# goprocontrol.net
KiCad netlist of a schematic drawn in EAGLE
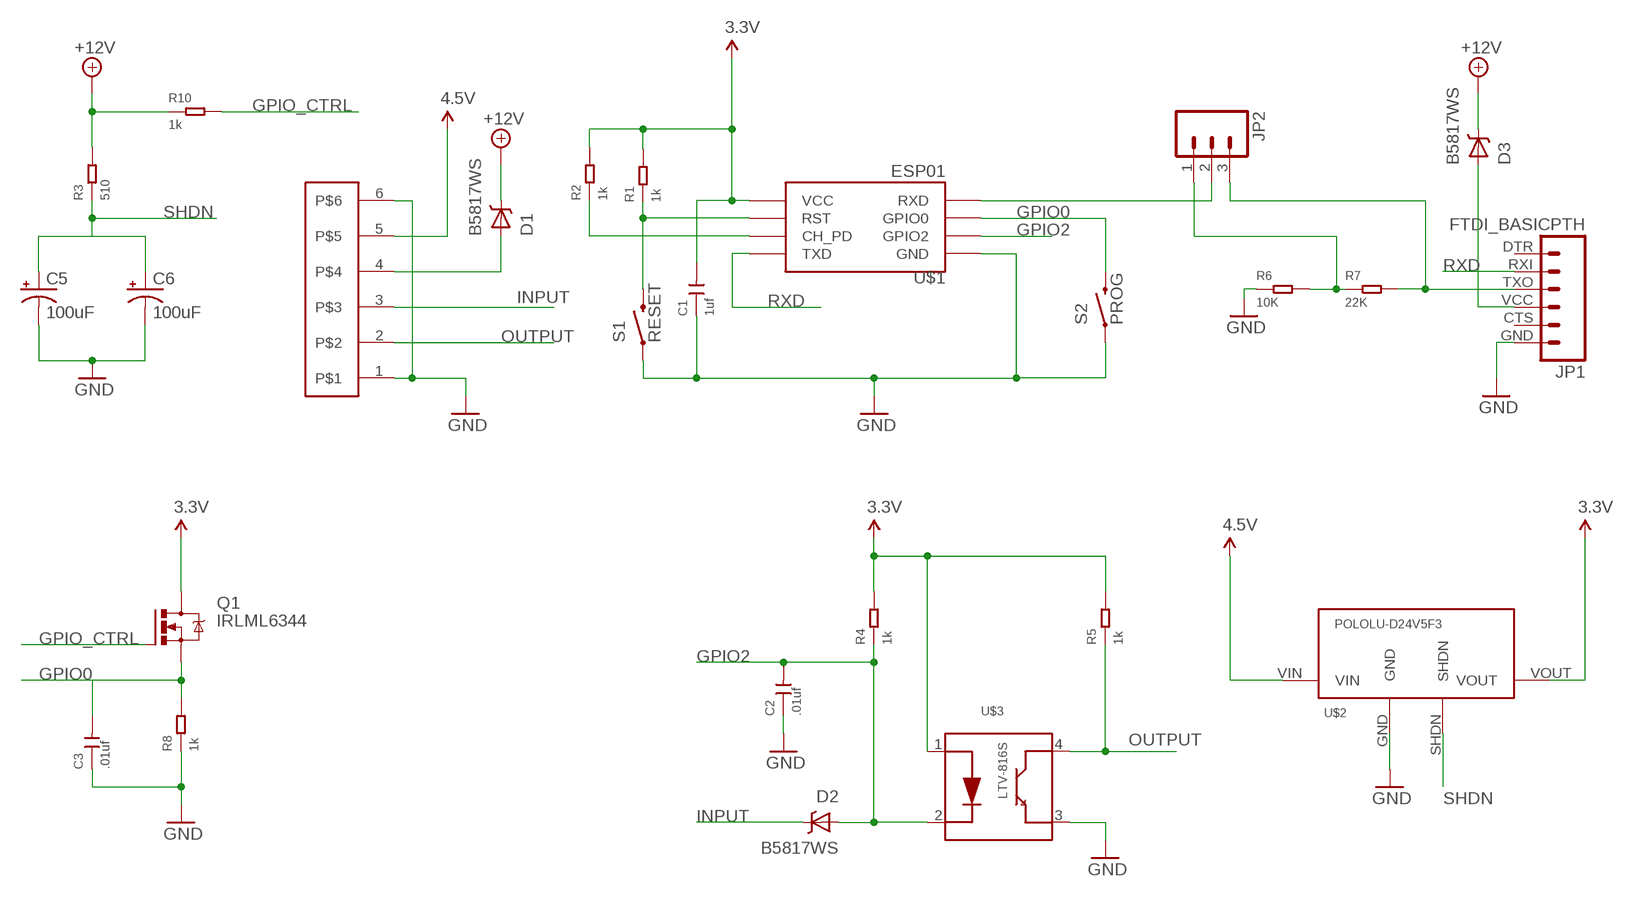
[diagram p0: schematic, sheet 1]

(export (version "E")
  (design (tool "Eeschema 10.0.6"))
  (components
    (comp (ref "C1")
      (value "1uf")
      (footprint "eagle-import:C0805")
      (fields (field (name "MPN") "CC0805KKX7R8BB105"))
      (libsource (lib "eagle-import") (part "CERAMIC-1UF-25V-10%-X7R(0805)"))
    )
    (comp (ref "C2")
      (value ".01uf")
      (footprint "eagle-import:C0805")
      (fields (field (name "MPN") "CC0805KKX7R8BB105"))
      (libsource (lib "eagle-import") (part "CERAMIC-1UF-25V-10%-X7R(0805)"))
    )
    (comp (ref "C3")
      (value ".01uf")
      (footprint "eagle-import:C0805")
      (fields (field (name "MPN") "CC0805KKX7R8BB105"))
      (libsource (lib "eagle-import") (part "CERAMIC-1UF-25V-10%-X7R(0805)"))
    )
    (comp (ref "C5")
      (value "100uF")
      (footprint "eagle-import:CPOL-RADIAL-100UF-25V")
      (libsource (lib "eagle-import") (part "CAP_POLPTH1"))
    )
    (comp (ref "C6")
      (value "100uF")
      (footprint "eagle-import:CPOL-RADIAL-100UF-25V")
      (libsource (lib "eagle-import") (part "CAP_POLPTH1"))
    )
    (comp (ref "D1")
      (value "B5817WS")
      (footprint "eagle-import:SOD-323")
      (libsource (lib "eagle-import") (part "SCHOTTKY-DIODE"))
    )
    (comp (ref "D2")
      (value "B5817WS")
      (footprint "eagle-import:SOD-323")
      (libsource (lib "eagle-import") (part "SCHOTTKY-DIODE"))
    )
    (comp (ref "D3")
      (value "B5817WS")
      (footprint "eagle-import:SOD-323")
      (libsource (lib "eagle-import") (part "SCHOTTKY-DIODE"))
    )
    (comp (ref "JP1")
      (value "FTDI_BASICPTH")
      (footprint "eagle-import:FTDI_BASIC")
      (libsource (lib "eagle-import") (part "FTDI_BASICPTH"))
    )
    (comp (ref "JP2")
      (value "M03PTH")
      (footprint "eagle-import:1X03")
      (libsource (lib "eagle-import") (part "M03PTH"))
    )
    (comp (ref "Q1")
      (value "IRLML6344")
      (footprint "eagle-import:SOT23")
      (libsource (lib "eagle-import") (part "IRLML6344"))
    )
    (comp (ref "R1")
      (value "1k")
      (footprint "eagle-import:R0805")
      (fields (field (name "MPN") "RC0805FR-0710KL"))
      (libsource (lib "eagle-import") (part "SMD-RES-10K-1%-1/8W(0805)"))
    )
    (comp (ref "R2")
      (value "1k")
      (footprint "eagle-import:R0805")
      (fields (field (name "MPN") "RC0805FR-0710KL"))
      (libsource (lib "eagle-import") (part "SMD-RES-10K-1%-1/8W(0805)"))
    )
    (comp (ref "R3")
      (value "510")
      (footprint "eagle-import:R0805")
      (fields (field (name "MPN") "RC0805FR-0710KL"))
      (libsource (lib "eagle-import") (part "SMD-RES-10K-1%-1/8W(0805)"))
    )
    (comp (ref "R4")
      (value "1k")
      (footprint "eagle-import:R0805")
      (fields (field (name "MPN") "RC0805FR-0710KL"))
      (libsource (lib "eagle-import") (part "SMD-RES-10K-1%-1/8W(0805)"))
    )
    (comp (ref "R5")
      (value "1k")
      (footprint "eagle-import:R0805")
      (fields (field (name "MPN") "RC0805FR-0710KL"))
      (libsource (lib "eagle-import") (part "SMD-RES-10K-1%-1/8W(0805)"))
    )
    (comp (ref "R6")
      (value "10K")
      (footprint "eagle-import:R0805")
      (fields (field (name "MPN") "RC0805FR-0710KL"))
      (libsource (lib "eagle-import") (part "SMD-RES-10K-1%-1/8W(0805)"))
    )
    (comp (ref "R7")
      (value "22K")
      (footprint "eagle-import:R0805")
      (fields (field (name "MPN") "RC0805JR-0722KL"))
      (libsource (lib "eagle-import") (part "SMD-RES-22K-5%-1/8W(0805)"))
    )
    (comp (ref "R8")
      (value "1k")
      (footprint "eagle-import:R0805")
      (fields (field (name "MPN") "RC0805FR-07100KL"))
      (libsource (lib "eagle-import") (part "SMD-RES-100K-1%-1/8W(0805)"))
    )
    (comp (ref "R10")
      (value "1k")
      (footprint "eagle-import:R0805")
      (fields (field (name "MPN") "RC0805FR-0710KL"))
      (libsource (lib "eagle-import") (part "SMD-RES-10K-1%-1/8W(0805)"))
    )
    (comp (ref "S1")
      (value "RESET")
      (footprint "eagle-import:TACTILE-PTH")
      (libsource (lib "eagle-import") (part "SWITCH-MOMENTARY-2PTH"))
    )
    (comp (ref "S2")
      (value "PROG")
      (footprint "eagle-import:TACTILE-PTH")
      (libsource (lib "eagle-import") (part "SWITCH-MOMENTARY-2PTH"))
    )
    (comp (ref "U$1")
      (value "ESP01")
      (footprint "eagle-import:ESP01")
      (libsource (lib "eagle-import") (part "ESP01"))
    )
    (comp (ref "U$2")
      (value "POLOLU-D24V5F3")
      (footprint "eagle-import:POLOLU-D24V5FX")
      (libsource (lib "eagle-import") (part "POLOLU-D24V5FD24V5F"))
    )
    (comp (ref "U$3")
      (value "LTV-816S")
      (footprint "eagle-import:SMD4-2.54-4.6X6.5MM")
      (libsource (lib "eagle-import") (part "SMD-PHOTOCOUPLER-5KV-LTV-816S(4P-4.6X6.5MM)"))
    )
    (comp (ref "U$4")
      (value "TERM-BLOCK-P6-3.5")
      (footprint "eagle-import:TERM-6P-3.5")
      (libsource (lib "eagle-import") (part "TERM-BLOCK-P6-3.5"))
    )
  )
  (nets
    (net (code "1") (name "+12V") (class "Default")
      (node (ref "D1") (pin "C1") (pinfunction "C_C1") (pintype "output"))
      (node (ref "D3") (pin "C1") (pinfunction "C_C1") (pintype "output"))
      (node (ref "R10") (pin "1") (pinfunction "1_1") (pintype "passive"))
      (node (ref "R3") (pin "2") (pinfunction "2_2") (pintype "passive"))
    )
    (net (code "2") (name "/GPIO0") (class "Default")
      (node (ref "C3") (pin "2") (pinfunction "2_2") (pintype "passive"))
      (node (ref "Q1") (pin "2") (pinfunction "S_2") (pintype "passive"))
      (node (ref "R8") (pin "2") (pinfunction "2_2") (pintype "passive"))
      (node (ref "S2") (pin "3") (pinfunction "2_3") (pintype "passive"))
      (node (ref "U$1") (pin "GPIO0") (pinfunction "GPIO0_GPIO0") (pintype "bidirectional"))
    )
    (net (code "3") (name "/GPIO2") (class "Default")
      (node (ref "C2") (pin "2") (pinfunction "2_2") (pintype "passive"))
      (node (ref "D2") (pin "A1") (pinfunction "A_A1") (pintype "input"))
      (node (ref "R4") (pin "1") (pinfunction "1_1") (pintype "passive"))
      (node (ref "U$1") (pin "GPIO2") (pinfunction "GPIO2_GPIO2") (pintype "bidirectional"))
      (node (ref "U$3") (pin "2") (pinfunction "CATHODE_2") (pintype "bidirectional"))
    )
    (net (code "4") (name "/GPIO_CTRL") (class "Default")
      (node (ref "Q1") (pin "1") (pinfunction "G_1") (pintype "passive"))
      (node (ref "R10") (pin "2") (pinfunction "2_2") (pintype "passive"))
    )
    (net (code "5") (name "/INPUT") (class "Default")
      (node (ref "D2") (pin "C1") (pinfunction "C_C1") (pintype "output"))
      (node (ref "U$4") (pin "3") (pinfunction "P$3_3") (pintype "bidirectional"))
    )
    (net (code "6") (name "/OUTPUT") (class "Default")
      (node (ref "R5") (pin "1") (pinfunction "1_1") (pintype "passive"))
      (node (ref "U$3") (pin "4") (pinfunction "COLLECTOR_4") (pintype "bidirectional"))
      (node (ref "U$4") (pin "2") (pinfunction "P$2_2") (pintype "bidirectional"))
    )
    (net (code "7") (name "/RXD") (class "Default")
      (node (ref "JP1") (pin "RXI") (pinfunction "2_RXI") (pintype "passive"))
      (node (ref "U$1") (pin "TX") (pinfunction "TXD_TX") (pintype "bidirectional"))
    )
    (net (code "8") (name "/SHDN") (class "Default")
      (node (ref "C5") (pin "1") (pinfunction "+_1") (pintype "passive"))
      (node (ref "C6") (pin "1") (pinfunction "+_1") (pintype "passive"))
      (node (ref "R3") (pin "1") (pinfunction "1_1") (pintype "passive"))
      (node (ref "U$2") (pin "SHDN") (pinfunction "SHDN_SHDN") (pintype "input"))
    )
    (net (code "9") (name "3.3V") (class "Default")
      (node (ref "C1") (pin "2") (pinfunction "2_2") (pintype "passive"))
      (node (ref "Q1") (pin "3") (pinfunction "D_3") (pintype "passive"))
      (node (ref "R1") (pin "2") (pinfunction "2_2") (pintype "passive"))
      (node (ref "R2") (pin "2") (pinfunction "2_2") (pintype "passive"))
      (node (ref "R4") (pin "2") (pinfunction "2_2") (pintype "passive"))
      (node (ref "R5") (pin "2") (pinfunction "2_2") (pintype "passive"))
      (node (ref "U$1") (pin "VCC") (pinfunction "VCC_VCC") (pintype "bidirectional"))
      (node (ref "U$2") (pin "VOUT") (pinfunction "VOUT_VOUT") (pintype "power_in"))
      (node (ref "U$3") (pin "1") (pinfunction "ANODE_1") (pintype "bidirectional"))
    )
    (net (code "10") (name "4.5V") (class "Default")
      (node (ref "U$2") (pin "VIN") (pinfunction "VIN_VIN") (pintype "input"))
      (node (ref "U$4") (pin "5") (pinfunction "P$5_5") (pintype "bidirectional"))
    )
    (net (code "11") (name "GND") (class "Default")
      (node (ref "C1") (pin "1") (pinfunction "1_1") (pintype "passive"))
      (node (ref "C2") (pin "1") (pinfunction "1_1") (pintype "passive"))
      (node (ref "C3") (pin "1") (pinfunction "1_1") (pintype "passive"))
      (node (ref "C5") (pin "2") (pinfunction "-_2") (pintype "passive"))
      (node (ref "C6") (pin "2") (pinfunction "-_2") (pintype "passive"))
      (node (ref "JP1") (pin "GND") (pinfunction "6_GND") (pintype "passive"))
      (node (ref "R6") (pin "1") (pinfunction "1_1") (pintype "passive"))
      (node (ref "R8") (pin "1") (pinfunction "1_1") (pintype "passive"))
      (node (ref "S1") (pin "1") (pinfunction "1_1") (pintype "passive"))
      (node (ref "S2") (pin "1") (pinfunction "1_1") (pintype "passive"))
      (node (ref "U$1") (pin "GND") (pinfunction "GND_GND") (pintype "bidirectional"))
      (node (ref "U$2") (pin "GND") (pinfunction "GND_GND") (pintype "power_in"))
      (node (ref "U$3") (pin "3") (pinfunction "EMITER_3") (pintype "bidirectional"))
      (node (ref "U$4") (pin "1") (pinfunction "P$1_1") (pintype "bidirectional"))
      (node (ref "U$4") (pin "6") (pinfunction "P$6_6") (pintype "bidirectional"))
    )
    (net (code "12") (name "Net-(D1-A)") (class "Default")
      (node (ref "D1") (pin "A1") (pinfunction "A_A1") (pintype "input"))
      (node (ref "U$4") (pin "4") (pinfunction "P$4_4") (pintype "bidirectional"))
    )
    (net (code "13") (name "Net-(D3-A)") (class "Default")
      (node (ref "D3") (pin "A1") (pinfunction "A_A1") (pintype "input"))
      (node (ref "JP1") (pin "VCC") (pinfunction "4_VCC") (pintype "passive"))
    )
    (net (code "14") (name "Net-(JP1-3)") (class "Default")
      (node (ref "JP1") (pin "TXO") (pinfunction "3_TXO") (pintype "passive"))
      (node (ref "JP2") (pin "3") (pinfunction "3_3") (pintype "passive"))
      (node (ref "R7") (pin "2") (pinfunction "2_2") (pintype "passive"))
    )
    (net (code "15") (name "Net-(JP2-Pad1)") (class "Default")
      (node (ref "JP2") (pin "1") (pinfunction "1_1") (pintype "passive"))
      (node (ref "R6") (pin "2") (pinfunction "2_2") (pintype "passive"))
      (node (ref "R7") (pin "1") (pinfunction "1_1") (pintype "passive"))
    )
    (net (code "16") (name "Net-(R2-Pad1)") (class "Default")
      (node (ref "R2") (pin "1") (pinfunction "1_1") (pintype "passive"))
      (node (ref "U$1") (pin "CH_PD") (pinfunction "CH_PD_CH_PD") (pintype "bidirectional"))
    )
    (net (code "17") (name "Net-(S1-2)") (class "Default")
      (node (ref "R1") (pin "1") (pinfunction "1_1") (pintype "passive"))
      (node (ref "S1") (pin "3") (pinfunction "2_3") (pintype "passive"))
      (node (ref "U$1") (pin "RST") (pinfunction "RST_RST") (pintype "bidirectional"))
    )
    (net (code "18") (name "Net-(U$1-RXD)") (class "Default")
      (node (ref "JP2") (pin "2") (pinfunction "2_2") (pintype "passive"))
      (node (ref "U$1") (pin "RX") (pinfunction "RXD_RX") (pintype "bidirectional"))
    )
    (net (code "19") (name "unconnected-(JP1-1-PadDTR)") (class "Default")
      (node (ref "JP1") (pin "DTR") (pinfunction "1_DTR") (pintype "passive"))
    )
    (net (code "20") (name "unconnected-(JP1-5-PadCTS)") (class "Default")
      (node (ref "JP1") (pin "CTS") (pinfunction "5_CTS") (pintype "passive"))
    )
  )
)
